# Rxxx.net
KiCad netlist of a schematic drawn in EAGLE
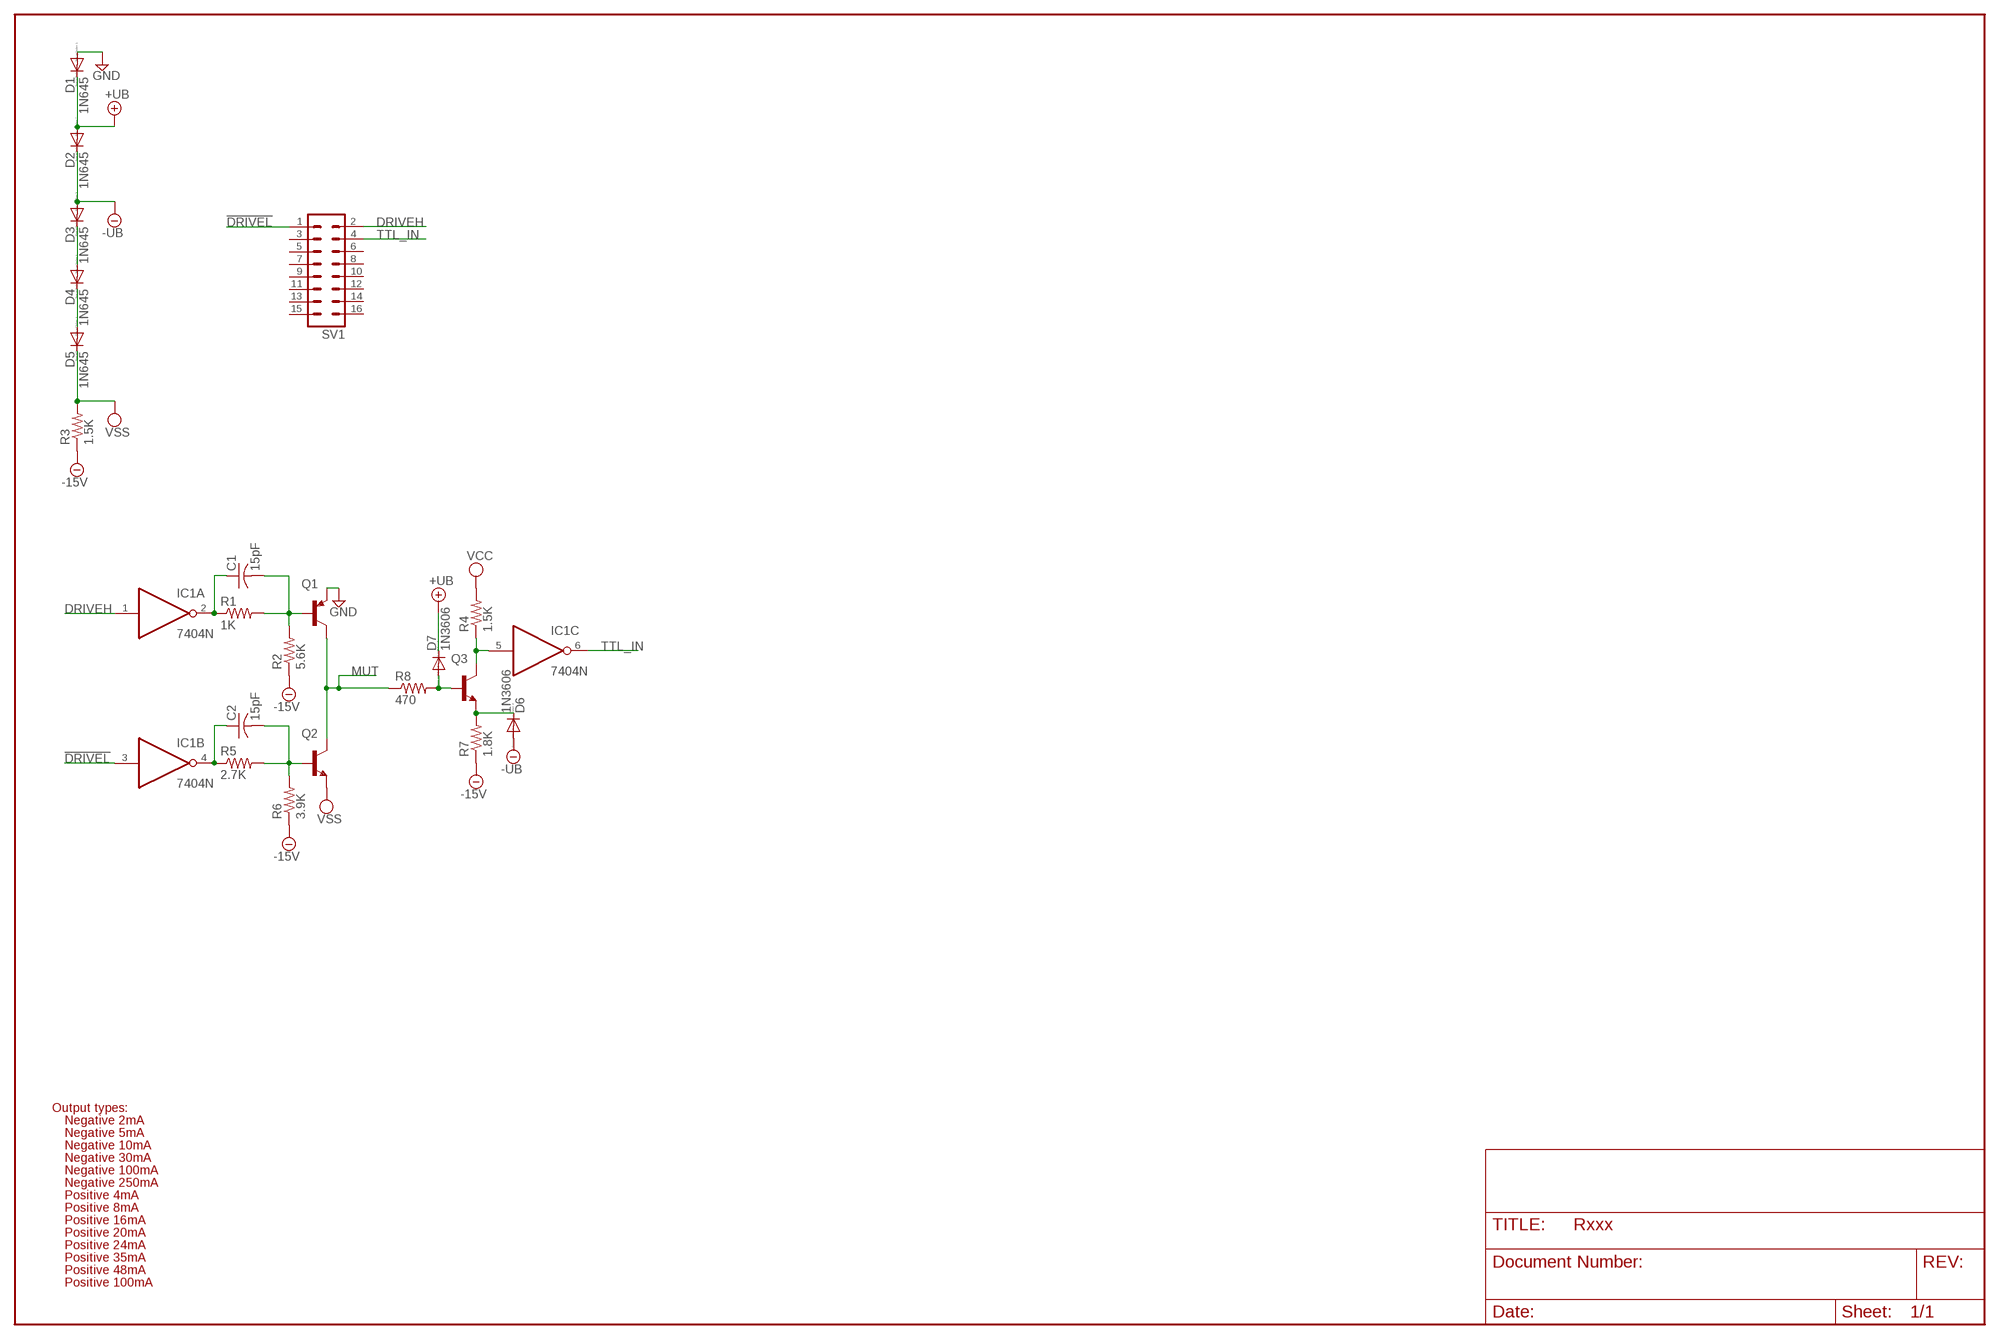
[diagram p0: schematic, sheet 1]

(export (version "E")
  (design (tool "Eeschema 10.0.6"))
  (components
    (comp (ref "C1")
      (value "15pF")
      (footprint "eagle-import:C050-025X075")
      (libsource (lib "eagle-import") (part "C-US050-025X075"))
    )
    (comp (ref "C2")
      (value "15pF")
      (footprint "eagle-import:C050-025X075")
      (libsource (lib "eagle-import") (part "C-US050-025X075"))
    )
    (comp (ref "D1")
      (value "1N645")
      (footprint "eagle-import:DO35-10")
      (libsource (lib "eagle-import") (part "DIODE-DO35-10"))
    )
    (comp (ref "D2")
      (value "1N645")
      (footprint "eagle-import:DO35-10")
      (libsource (lib "eagle-import") (part "DIODE-DO35-10"))
    )
    (comp (ref "D3")
      (value "1N645")
      (footprint "eagle-import:DO35-10")
      (libsource (lib "eagle-import") (part "DIODE-DO35-10"))
    )
    (comp (ref "D4")
      (value "1N645")
      (footprint "eagle-import:DO35-10")
      (libsource (lib "eagle-import") (part "DIODE-DO35-10"))
    )
    (comp (ref "D5")
      (value "1N645")
      (footprint "eagle-import:DO35-10")
      (libsource (lib "eagle-import") (part "DIODE-DO35-10"))
    )
    (comp (ref "D6")
      (value "1N3606")
      (footprint "eagle-import:DO35-10")
      (libsource (lib "eagle-import") (part "DIODE-DO35-10"))
    )
    (comp (ref "D7")
      (value "1N3606")
      (footprint "eagle-import:DO35-10")
      (libsource (lib "eagle-import") (part "DIODE-DO35-10"))
    )
    (comp (ref "IC1")
      (value "7404N")
      (footprint "eagle-import:DIL14")
      (libsource (lib "eagle-import") (part "7404N"))
    )
    (comp (ref "Q1")
      (value "-PNP-TO5")
      (footprint "eagle-import:TO5")
      (libsource (lib "eagle-import") (part "-PNP-TO5"))
    )
    (comp (ref "Q2")
      (value "-NPN-TO5")
      (footprint "eagle-import:TO5")
      (libsource (lib "eagle-import") (part "-NPN-TO5"))
    )
    (comp (ref "Q3")
      (value "-NPN-TO5")
      (footprint "eagle-import:TO5")
      (libsource (lib "eagle-import") (part "-NPN-TO5"))
    )
    (comp (ref "R1")
      (value "1K")
      (footprint "eagle-import:0207_10")
      (libsource (lib "eagle-import") (part "R-US_0207/10"))
    )
    (comp (ref "R2")
      (value "5.6K")
      (footprint "eagle-import:0207_10")
      (libsource (lib "eagle-import") (part "R-US_0207/10"))
    )
    (comp (ref "R3")
      (value "1.5K")
      (footprint "eagle-import:0207_10")
      (libsource (lib "eagle-import") (part "R-US_0207/10"))
    )
    (comp (ref "R4")
      (value "1.5K")
      (footprint "eagle-import:0207_10")
      (libsource (lib "eagle-import") (part "R-US_0207/10"))
    )
    (comp (ref "R5")
      (value "2.7K")
      (footprint "eagle-import:0207_10")
      (libsource (lib "eagle-import") (part "R-US_0207/10"))
    )
    (comp (ref "R6")
      (value "3.9K")
      (footprint "eagle-import:0207_10")
      (libsource (lib "eagle-import") (part "R-US_0207/10"))
    )
    (comp (ref "R7")
      (value "1.8K")
      (footprint "eagle-import:0207_10")
      (libsource (lib "eagle-import") (part "R-US_0207/10"))
    )
    (comp (ref "R8")
      (value "470")
      (footprint "eagle-import:0207_10")
      (libsource (lib "eagle-import") (part "R-US_0207/10"))
    )
    (comp (ref "SV1")
      (value "MA08-2")
      (footprint "eagle-import:MA08-2")
      (libsource (lib "eagle-import") (part "MA08-2"))
    )
  )
  (nets
    (net (code "1") (name "+UB") (class "Default")
      (node (ref "D1") (pin "C") (pinfunction "C_C") (pintype "passive"))
      (node (ref "D2") (pin "A") (pinfunction "A_A") (pintype "passive"))
      (node (ref "D7") (pin "C") (pinfunction "C_C") (pintype "passive"))
    )
    (net (code "2") (name "-15V") (class "Default")
      (node (ref "R2") (pin "1") (pinfunction "1_1") (pintype "passive"))
      (node (ref "R3") (pin "1") (pinfunction "1_1") (pintype "passive"))
      (node (ref "R6") (pin "1") (pinfunction "1_1") (pintype "passive"))
      (node (ref "R7") (pin "1") (pinfunction "1_1") (pintype "passive"))
    )
    (net (code "3") (name "-UB") (class "Default")
      (node (ref "D2") (pin "C") (pinfunction "C_C") (pintype "passive"))
      (node (ref "D3") (pin "A") (pinfunction "A_A") (pintype "passive"))
      (node (ref "D6") (pin "A") (pinfunction "A_A") (pintype "passive"))
    )
    (net (code "4") (name "/DRIVEH") (class "Default")
      (node (ref "IC1") (pin "1") (pinfunction "I_1") (pintype "input"))
      (node (ref "SV1") (pin "2") (pinfunction "2_2") (pintype "passive"))
    )
    (net (code "5") (name "/MUT") (class "Default")
      (node (ref "Q1") (pin "3") (pinfunction "C_3") (pintype "passive"))
      (node (ref "Q2") (pin "3") (pinfunction "C_3") (pintype "passive"))
      (node (ref "R8") (pin "1") (pinfunction "1_1") (pintype "passive"))
    )
    (net (code "6") (name "/TTL_IN") (class "Default")
      (node (ref "IC1") (pin "6") (pinfunction "O_6") (pintype "output"))
      (node (ref "SV1") (pin "4") (pinfunction "4_4") (pintype "passive"))
    )
    (net (code "7") (name "/~{DRIVEL}") (class "Default")
      (node (ref "IC1") (pin "3") (pinfunction "I_3") (pintype "input"))
      (node (ref "SV1") (pin "1") (pinfunction "1_1") (pintype "passive"))
    )
    (net (code "8") (name "GND") (class "Default")
      (node (ref "D1") (pin "A") (pinfunction "A_A") (pintype "passive"))
      (node (ref "Q1") (pin "1") (pinfunction "E_1") (pintype "passive"))
    )
    (net (code "9") (name "Net-(D3-PadC)") (class "Default")
      (node (ref "D3") (pin "C") (pinfunction "C_C") (pintype "passive"))
      (node (ref "D4") (pin "A") (pinfunction "A_A") (pintype "passive"))
    )
    (net (code "10") (name "Net-(D4-PadC)") (class "Default")
      (node (ref "D4") (pin "C") (pinfunction "C_C") (pintype "passive"))
      (node (ref "D5") (pin "A") (pinfunction "A_A") (pintype "passive"))
    )
    (net (code "11") (name "Net-(IC1A-O)") (class "Default")
      (node (ref "C1") (pin "1") (pinfunction "1_1") (pintype "passive"))
      (node (ref "IC1") (pin "2") (pinfunction "O_2") (pintype "output"))
      (node (ref "R1") (pin "1") (pinfunction "1_1") (pintype "passive"))
    )
    (net (code "12") (name "Net-(IC1B-O)") (class "Default")
      (node (ref "C2") (pin "1") (pinfunction "1_1") (pintype "passive"))
      (node (ref "IC1") (pin "4") (pinfunction "O_4") (pintype "output"))
      (node (ref "R5") (pin "1") (pinfunction "1_1") (pintype "passive"))
    )
    (net (code "13") (name "Net-(IC1C-I)") (class "Default")
      (node (ref "IC1") (pin "5") (pinfunction "I_5") (pintype "input"))
      (node (ref "Q3") (pin "3") (pinfunction "C_3") (pintype "passive"))
      (node (ref "R4") (pin "1") (pinfunction "1_1") (pintype "passive"))
    )
    (net (code "14") (name "Net-(Q1-B)") (class "Default")
      (node (ref "C1") (pin "2") (pinfunction "2_2") (pintype "passive"))
      (node (ref "Q1") (pin "2") (pinfunction "B_2") (pintype "passive"))
      (node (ref "R1") (pin "2") (pinfunction "2_2") (pintype "passive"))
      (node (ref "R2") (pin "2") (pinfunction "2_2") (pintype "passive"))
    )
    (net (code "15") (name "Net-(Q2-B)") (class "Default")
      (node (ref "C2") (pin "2") (pinfunction "2_2") (pintype "passive"))
      (node (ref "Q2") (pin "2") (pinfunction "B_2") (pintype "passive"))
      (node (ref "R5") (pin "2") (pinfunction "2_2") (pintype "passive"))
      (node (ref "R6") (pin "2") (pinfunction "2_2") (pintype "passive"))
    )
    (net (code "16") (name "Net-(Q3-B)") (class "Default")
      (node (ref "D7") (pin "A") (pinfunction "A_A") (pintype "passive"))
      (node (ref "Q3") (pin "2") (pinfunction "B_2") (pintype "passive"))
      (node (ref "R8") (pin "2") (pinfunction "2_2") (pintype "passive"))
    )
    (net (code "17") (name "Net-(Q3-E)") (class "Default")
      (node (ref "D6") (pin "C") (pinfunction "C_C") (pintype "passive"))
      (node (ref "Q3") (pin "1") (pinfunction "E_1") (pintype "passive"))
      (node (ref "R7") (pin "2") (pinfunction "2_2") (pintype "passive"))
    )
    (net (code "18") (name "VCC") (class "Default")
      (node (ref "R4") (pin "2") (pinfunction "2_2") (pintype "passive"))
    )
    (net (code "19") (name "VSS") (class "Default")
      (node (ref "D5") (pin "C") (pinfunction "C_C") (pintype "passive"))
      (node (ref "Q2") (pin "1") (pinfunction "E_1") (pintype "passive"))
      (node (ref "R3") (pin "2") (pinfunction "2_2") (pintype "passive"))
    )
    (net (code "20") (name "unconnected-(SV1-Pad3)") (class "Default")
      (node (ref "SV1") (pin "3") (pinfunction "3_3") (pintype "passive"))
    )
    (net (code "21") (name "unconnected-(SV1-Pad5)") (class "Default")
      (node (ref "SV1") (pin "5") (pinfunction "5_5") (pintype "passive"))
    )
    (net (code "22") (name "unconnected-(SV1-Pad6)") (class "Default")
      (node (ref "SV1") (pin "6") (pinfunction "6_6") (pintype "passive"))
    )
    (net (code "23") (name "unconnected-(SV1-Pad7)") (class "Default")
      (node (ref "SV1") (pin "7") (pinfunction "7_7") (pintype "passive"))
    )
    (net (code "24") (name "unconnected-(SV1-Pad8)") (class "Default")
      (node (ref "SV1") (pin "8") (pinfunction "8_8") (pintype "passive"))
    )
    (net (code "25") (name "unconnected-(SV1-Pad9)") (class "Default")
      (node (ref "SV1") (pin "9") (pinfunction "9_9") (pintype "passive"))
    )
    (net (code "26") (name "unconnected-(SV1-Pad10)") (class "Default")
      (node (ref "SV1") (pin "10") (pinfunction "10_10") (pintype "passive"))
    )
    (net (code "27") (name "unconnected-(SV1-Pad11)") (class "Default")
      (node (ref "SV1") (pin "11") (pinfunction "11_11") (pintype "passive"))
    )
    (net (code "28") (name "unconnected-(SV1-Pad12)") (class "Default")
      (node (ref "SV1") (pin "12") (pinfunction "12_12") (pintype "passive"))
    )
    (net (code "29") (name "unconnected-(SV1-Pad13)") (class "Default")
      (node (ref "SV1") (pin "13") (pinfunction "13_13") (pintype "passive"))
    )
    (net (code "30") (name "unconnected-(SV1-Pad14)") (class "Default")
      (node (ref "SV1") (pin "14") (pinfunction "14_14") (pintype "passive"))
    )
    (net (code "31") (name "unconnected-(SV1-Pad15)") (class "Default")
      (node (ref "SV1") (pin "15") (pinfunction "15_15") (pintype "passive"))
    )
    (net (code "32") (name "unconnected-(SV1-Pad16)") (class "Default")
      (node (ref "SV1") (pin "16") (pinfunction "16_16") (pintype "passive"))
    )
  )
)
